# IR_receiver_v10.net
KiCad netlist of a schematic drawn in EAGLE
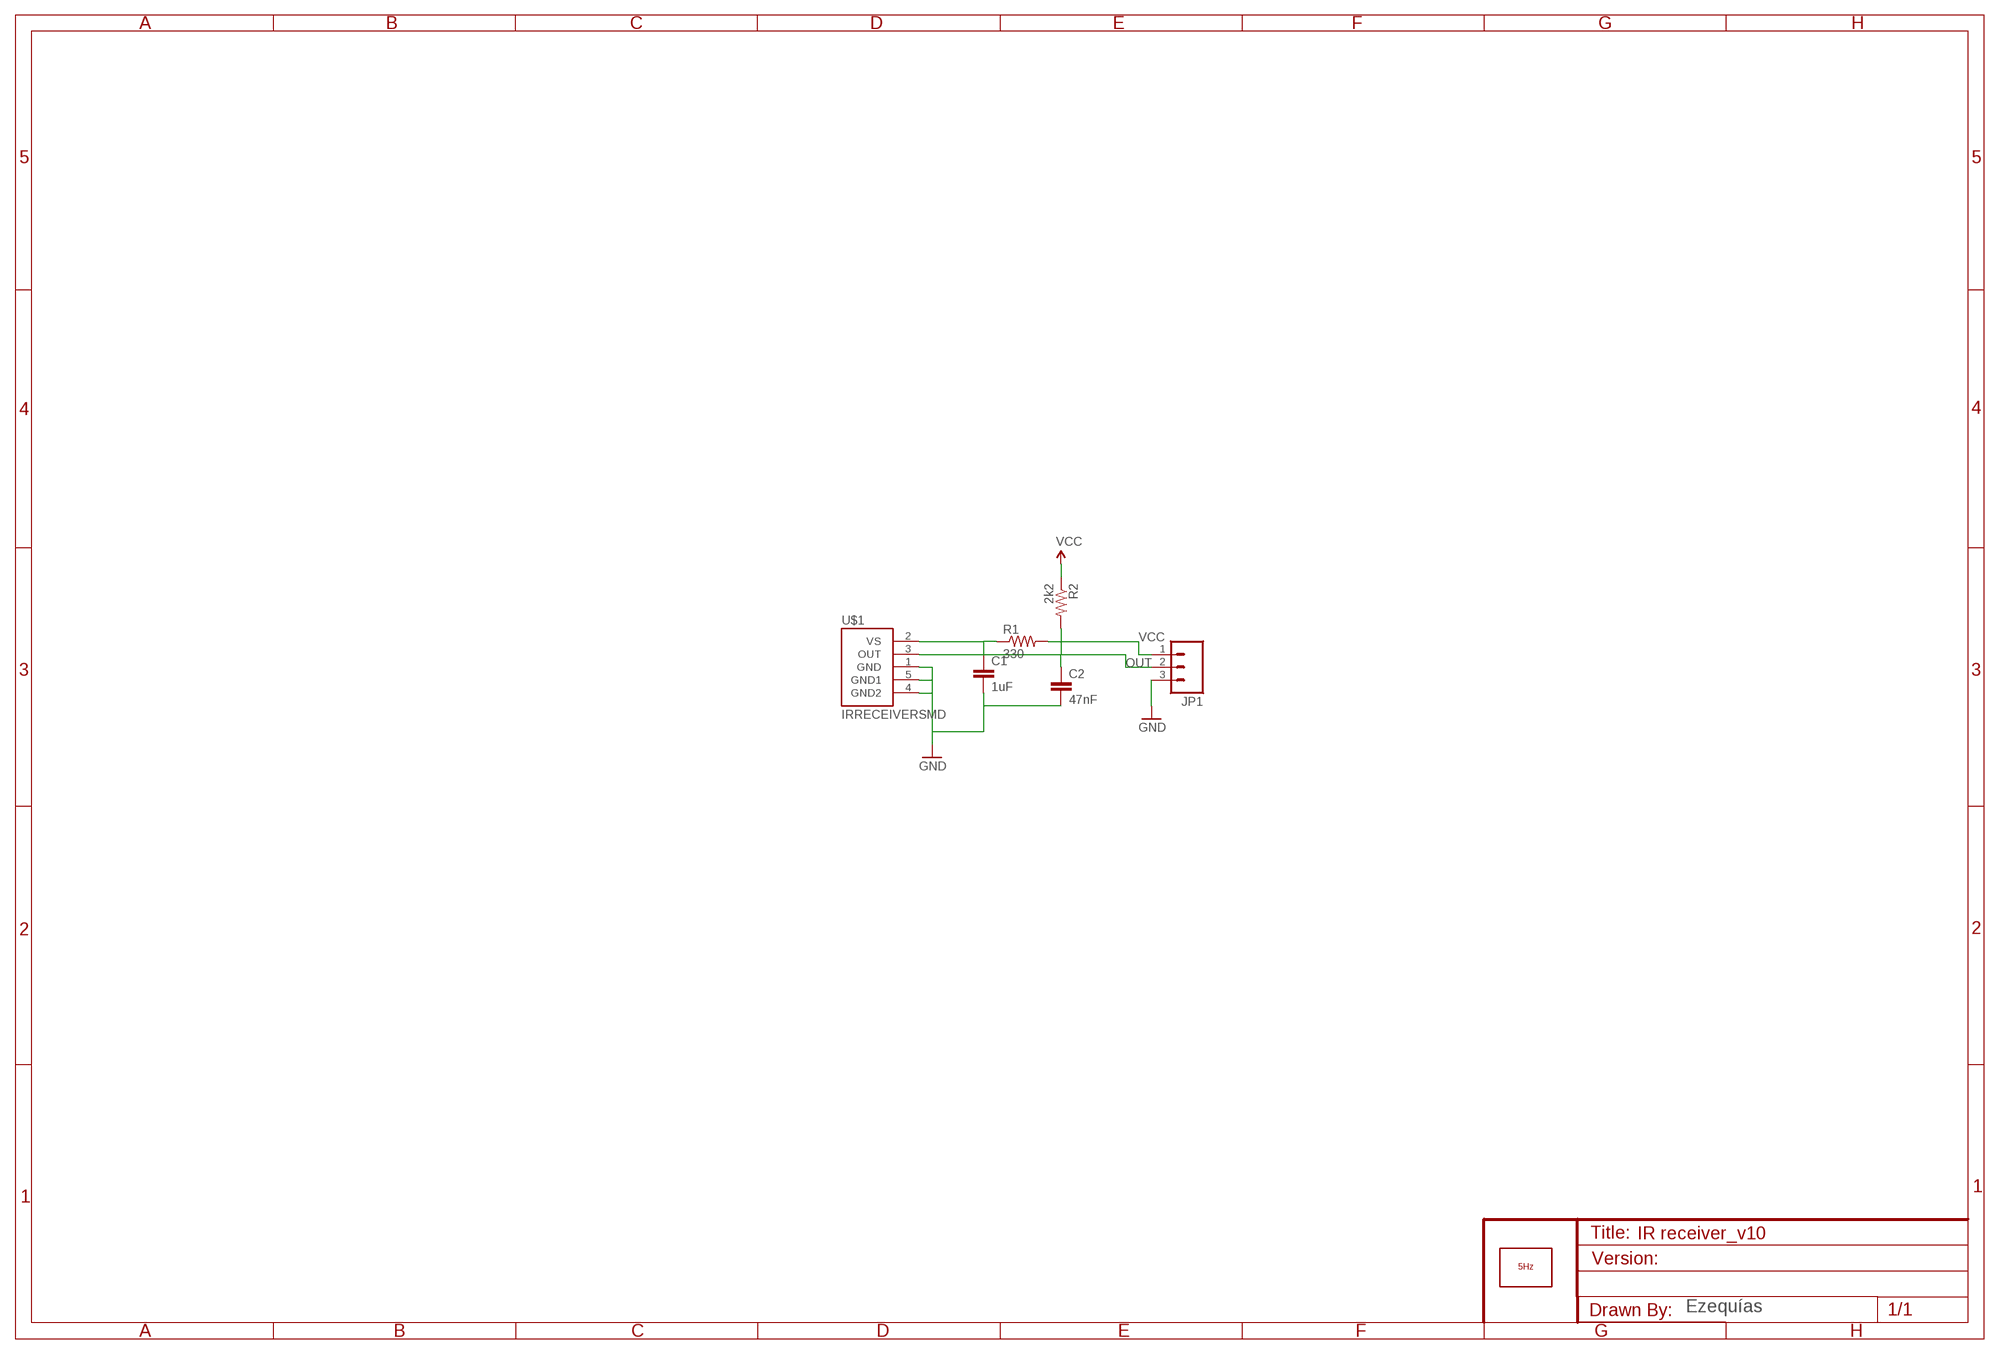
[diagram p0: schematic, sheet 1]

(export (version "E")
  (design (tool "Eeschema 10.0.6"))
  (components
    (comp (ref "C1")
      (value "1uF")
      (footprint "eagle-import:0603-CAP")
      (libsource (lib "eagle-import") (part "CAP0603-CAP"))
    )
    (comp (ref "C2")
      (value "47nF")
      (footprint "eagle-import:0603-CAP")
      (libsource (lib "eagle-import") (part "CAP0603-CAP"))
    )
    (comp (ref "JP1")
      (value "M03PTH")
      (footprint "eagle-import:1X03")
      (libsource (lib "eagle-import") (part "M03PTH"))
    )
    (comp (ref "LOGO1")
      (value "LOGO_5HZ_MAIN_5MM")
      (footprint "eagle-import:5HZ_LOGO_MAIN_5MM")
      (libsource (lib "eagle-import") (part "LOGO_5HZ_MAIN_5MM"))
    )
    (comp (ref "R1")
      (value "330")
      (footprint "eagle-import:0603-RES")
      (libsource (lib "eagle-import") (part "RESISTOR0603-RES"))
    )
    (comp (ref "R2")
      (value "2k2")
      (footprint "eagle-import:0603-RES")
      (libsource (lib "eagle-import") (part "RESISTOR0603-RES"))
    )
    (comp (ref "U$1")
      (value "IRRECEIVERSMD")
      (footprint "eagle-import:TSOP8523")
      (libsource (lib "eagle-import") (part "IRRECEIVERSMD"))
    )
  )
  (nets
    (net (code "1") (name "/OUT") (class "Default")
      (node (ref "C2") (pin "1") (pinfunction "1_1") (pintype "passive"))
      (node (ref "JP1") (pin "2") (pinfunction "2_2") (pintype "passive"))
      (node (ref "R2") (pin "2") (pinfunction "2_2") (pintype "passive"))
      (node (ref "U$1") (pin "3") (pinfunction "OUT_3") (pintype "bidirectional"))
    )
    (net (code "2") (name "GND") (class "Default")
      (node (ref "C1") (pin "2") (pinfunction "2_2") (pintype "passive"))
      (node (ref "C2") (pin "2") (pinfunction "2_2") (pintype "passive"))
      (node (ref "JP1") (pin "3") (pinfunction "3_3") (pintype "passive"))
      (node (ref "U$1") (pin "1") (pinfunction "GND_1") (pintype "bidirectional"))
      (node (ref "U$1") (pin "4") (pinfunction "GND2_4") (pintype "bidirectional"))
      (node (ref "U$1") (pin "5") (pinfunction "GND1_5") (pintype "bidirectional"))
    )
    (net (code "3") (name "Net-(U$1-VS)") (class "Default")
      (node (ref "C1") (pin "1") (pinfunction "1_1") (pintype "passive"))
      (node (ref "R1") (pin "1") (pinfunction "1_1") (pintype "passive"))
      (node (ref "U$1") (pin "2") (pinfunction "VS_2") (pintype "bidirectional"))
    )
    (net (code "4") (name "VCC") (class "Default")
      (node (ref "JP1") (pin "1") (pinfunction "1_1") (pintype "passive"))
      (node (ref "R1") (pin "2") (pinfunction "2_2") (pintype "passive"))
      (node (ref "R2") (pin "1") (pinfunction "1_1") (pintype "passive"))
    )
  )
)
